# RFM70.net
KiCad netlist of a schematic drawn in EAGLE
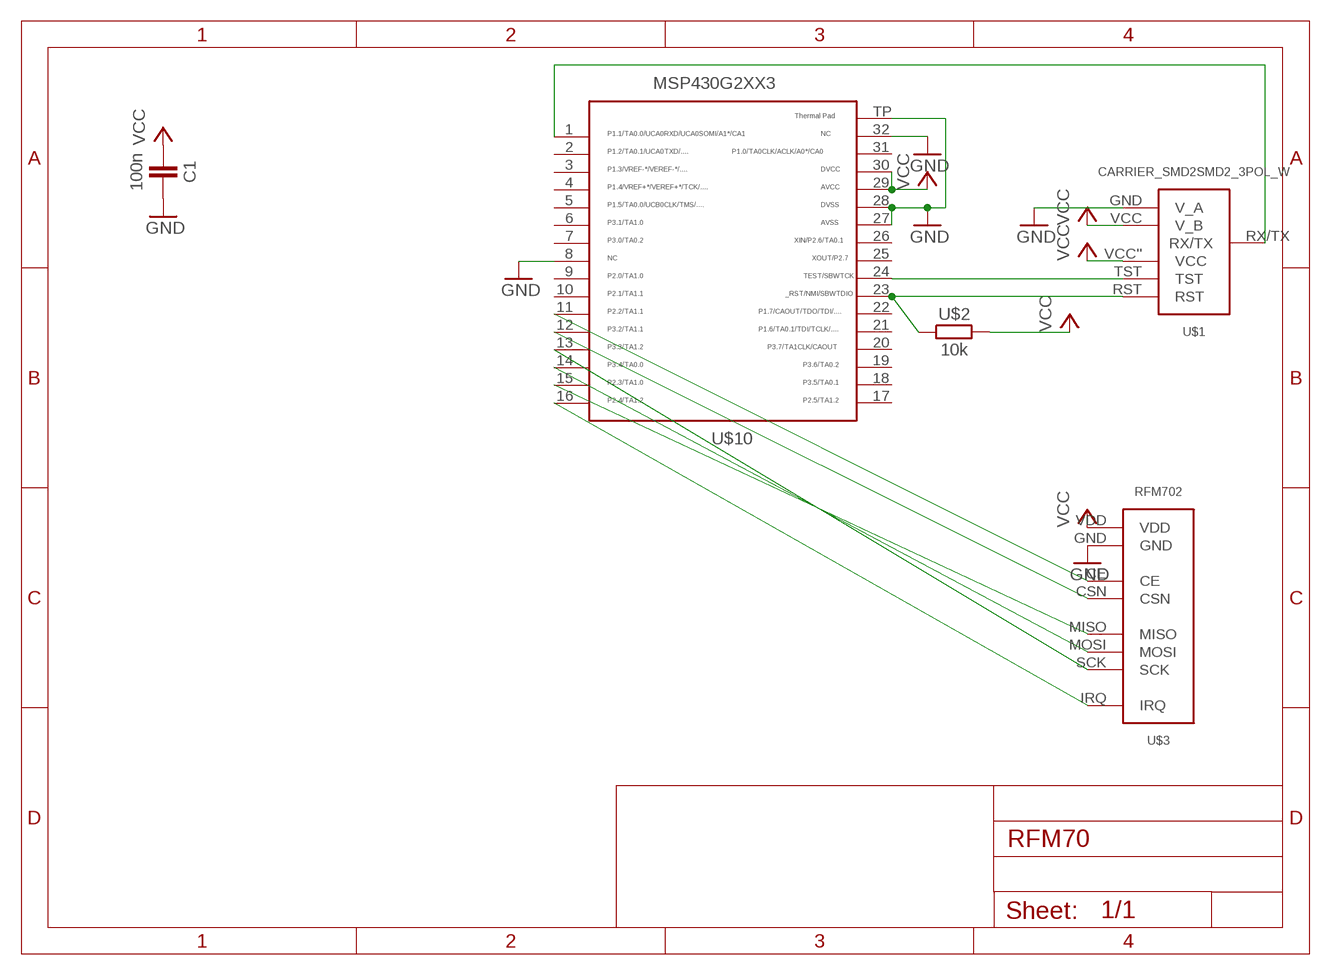
[diagram p0: schematic, sheet 1]

(export (version "E")
  (design (tool "Eeschema 10.0.6"))
  (components
    (comp (ref "C1")
      (value "100n")
      (footprint "eagle-import:603")
      (libsource (lib "eagle-import") (part "CAPACITOR"))
    )
    (comp (ref "U$1")
      (value "CARRIER_SMD2SMD2_3POL_W")
      (footprint "eagle-import:CARRIER_SMD2_WIDE_3POL")
      (libsource (lib "eagle-import") (part "CARRIER_SMD2SMD2_3POL_W"))
    )
    (comp (ref "U$2")
      (value "10k")
      (footprint "eagle-import:603")
      (libsource (lib "eagle-import") (part "RESISTOR0603"))
    )
    (comp (ref "U$3")
      (value "RFM702")
      (footprint "eagle-import:RFM70_SMD")
      (libsource (lib "eagle-import") (part "RFM702"))
    )
    (comp (ref "U$10")
      (value "MSP430G2553")
      (footprint "eagle-import:QFN32")
      (libsource (lib "eagle-import") (part "MSP430G2553"))
    )
  )
  (nets
    (net (code "1") (name "GND") (class "Default")
      (node (ref "C1") (pin "2") (pinfunction "2_2") (pintype "passive"))
      (node (ref "U$1") (pin "GND") (pinfunction "V_A_GND") (pintype "bidirectional"))
      (node (ref "U$10") (pin "27") (pinfunction "27_27") (pintype "bidirectional"))
      (node (ref "U$10") (pin "28") (pinfunction "28_28") (pintype "bidirectional"))
      (node (ref "U$10") (pin "32") (pinfunction "32_32") (pintype "bidirectional"))
      (node (ref "U$10") (pin "8") (pinfunction "8_8") (pintype "bidirectional"))
      (node (ref "U$10") (pin "TP") (pinfunction "TP_TP") (pintype "bidirectional"))
      (node (ref "U$3") (pin "GND") (pinfunction "GND_GND") (pintype "bidirectional"))
    )
    (net (code "2") (name "Net-(U$1-PadRST)") (class "Default")
      (node (ref "U$1") (pin "RST") (pinfunction "RST_RST") (pintype "bidirectional"))
      (node (ref "U$10") (pin "23") (pinfunction "23_23") (pintype "bidirectional"))
      (node (ref "U$2") (pin "1") (pinfunction "1_1") (pintype "passive"))
    )
    (net (code "3") (name "Net-(U$1-PadRX{slash}TX)") (class "Default")
      (node (ref "U$1") (pin "RX/TX") (pinfunction "RX/TX_RX/TX") (pintype "bidirectional"))
      (node (ref "U$10") (pin "1") (pinfunction "1_1") (pintype "bidirectional"))
    )
    (net (code "4") (name "Net-(U$1-PadTST)") (class "Default")
      (node (ref "U$1") (pin "TST") (pinfunction "TST_TST") (pintype "bidirectional"))
      (node (ref "U$10") (pin "24") (pinfunction "24_24") (pintype "bidirectional"))
    )
    (net (code "5") (name "Net-(U$10-Pad11)") (class "Default")
      (node (ref "U$10") (pin "11") (pinfunction "11_11") (pintype "bidirectional"))
      (node (ref "U$3") (pin "CE") (pinfunction "CE_CE") (pintype "bidirectional"))
    )
    (net (code "6") (name "Net-(U$10-Pad12)") (class "Default")
      (node (ref "U$10") (pin "12") (pinfunction "12_12") (pintype "bidirectional"))
      (node (ref "U$3") (pin "CSN") (pinfunction "CSN_CSN") (pintype "bidirectional"))
    )
    (net (code "7") (name "Net-(U$10-Pad13)") (class "Default")
      (node (ref "U$10") (pin "13") (pinfunction "13_13") (pintype "bidirectional"))
      (node (ref "U$3") (pin "SCK") (pinfunction "SCK_SCK") (pintype "bidirectional"))
    )
    (net (code "8") (name "Net-(U$10-Pad14)") (class "Default")
      (node (ref "U$10") (pin "14") (pinfunction "14_14") (pintype "bidirectional"))
      (node (ref "U$3") (pin "MOSI") (pinfunction "MOSI_MOSI") (pintype "bidirectional"))
    )
    (net (code "9") (name "Net-(U$10-Pad15)") (class "Default")
      (node (ref "U$10") (pin "15") (pinfunction "15_15") (pintype "bidirectional"))
      (node (ref "U$3") (pin "MISO") (pinfunction "MISO_MISO") (pintype "bidirectional"))
    )
    (net (code "10") (name "Net-(U$10-Pad16)") (class "Default")
      (node (ref "U$10") (pin "16") (pinfunction "16_16") (pintype "bidirectional"))
      (node (ref "U$3") (pin "IRQ") (pinfunction "IRQ_IRQ") (pintype "bidirectional"))
    )
    (net (code "11") (name "VCC") (class "Default")
      (node (ref "C1") (pin "1") (pinfunction "1_1") (pintype "passive"))
      (node (ref "U$1") (pin "VCC") (pinfunction "V_B_VCC") (pintype "bidirectional"))
      (node (ref "U$1") (pin "VCC''") (pinfunction "VCC_VCC''") (pintype "bidirectional"))
      (node (ref "U$10") (pin "29") (pinfunction "29_29") (pintype "bidirectional"))
      (node (ref "U$10") (pin "30") (pinfunction "30_30") (pintype "bidirectional"))
      (node (ref "U$2") (pin "2") (pinfunction "2_2") (pintype "passive"))
      (node (ref "U$3") (pin "VDD") (pinfunction "VDD_VDD") (pintype "bidirectional"))
    )
    (net (code "12") (name "unconnected-(U$10-Pad2)") (class "Default")
      (node (ref "U$10") (pin "2") (pinfunction "2_2") (pintype "bidirectional"))
    )
    (net (code "13") (name "unconnected-(U$10-Pad3)") (class "Default")
      (node (ref "U$10") (pin "3") (pinfunction "3_3") (pintype "bidirectional"))
    )
    (net (code "14") (name "unconnected-(U$10-Pad4)") (class "Default")
      (node (ref "U$10") (pin "4") (pinfunction "4_4") (pintype "bidirectional"))
    )
    (net (code "15") (name "unconnected-(U$10-Pad5)") (class "Default")
      (node (ref "U$10") (pin "5") (pinfunction "5_5") (pintype "bidirectional"))
    )
    (net (code "16") (name "unconnected-(U$10-Pad6)") (class "Default")
      (node (ref "U$10") (pin "6") (pinfunction "6_6") (pintype "bidirectional"))
    )
    (net (code "17") (name "unconnected-(U$10-Pad7)") (class "Default")
      (node (ref "U$10") (pin "7") (pinfunction "7_7") (pintype "bidirectional"))
    )
    (net (code "18") (name "unconnected-(U$10-Pad9)") (class "Default")
      (node (ref "U$10") (pin "9") (pinfunction "9_9") (pintype "bidirectional"))
    )
    (net (code "19") (name "unconnected-(U$10-Pad10)") (class "Default")
      (node (ref "U$10") (pin "10") (pinfunction "10_10") (pintype "bidirectional"))
    )
    (net (code "20") (name "unconnected-(U$10-Pad17)") (class "Default")
      (node (ref "U$10") (pin "17") (pinfunction "17_17") (pintype "bidirectional"))
    )
    (net (code "21") (name "unconnected-(U$10-Pad18)") (class "Default")
      (node (ref "U$10") (pin "18") (pinfunction "18_18") (pintype "bidirectional"))
    )
    (net (code "22") (name "unconnected-(U$10-Pad19)") (class "Default")
      (node (ref "U$10") (pin "19") (pinfunction "19_19") (pintype "bidirectional"))
    )
    (net (code "23") (name "unconnected-(U$10-Pad20)") (class "Default")
      (node (ref "U$10") (pin "20") (pinfunction "20_20") (pintype "bidirectional"))
    )
    (net (code "24") (name "unconnected-(U$10-Pad21)") (class "Default")
      (node (ref "U$10") (pin "21") (pinfunction "21_21") (pintype "bidirectional"))
    )
    (net (code "25") (name "unconnected-(U$10-Pad22)") (class "Default")
      (node (ref "U$10") (pin "22") (pinfunction "22_22") (pintype "bidirectional"))
    )
    (net (code "26") (name "unconnected-(U$10-Pad25)") (class "Default")
      (node (ref "U$10") (pin "25") (pinfunction "25_25") (pintype "bidirectional"))
    )
    (net (code "27") (name "unconnected-(U$10-Pad26)") (class "Default")
      (node (ref "U$10") (pin "26") (pinfunction "26_26") (pintype "bidirectional"))
    )
    (net (code "28") (name "unconnected-(U$10-Pad31)") (class "Default")
      (node (ref "U$10") (pin "31") (pinfunction "31_31") (pintype "bidirectional"))
    )
  )
)
